# AP7387Q.net
KiCad netlist of a schematic drawn in Altium Designer
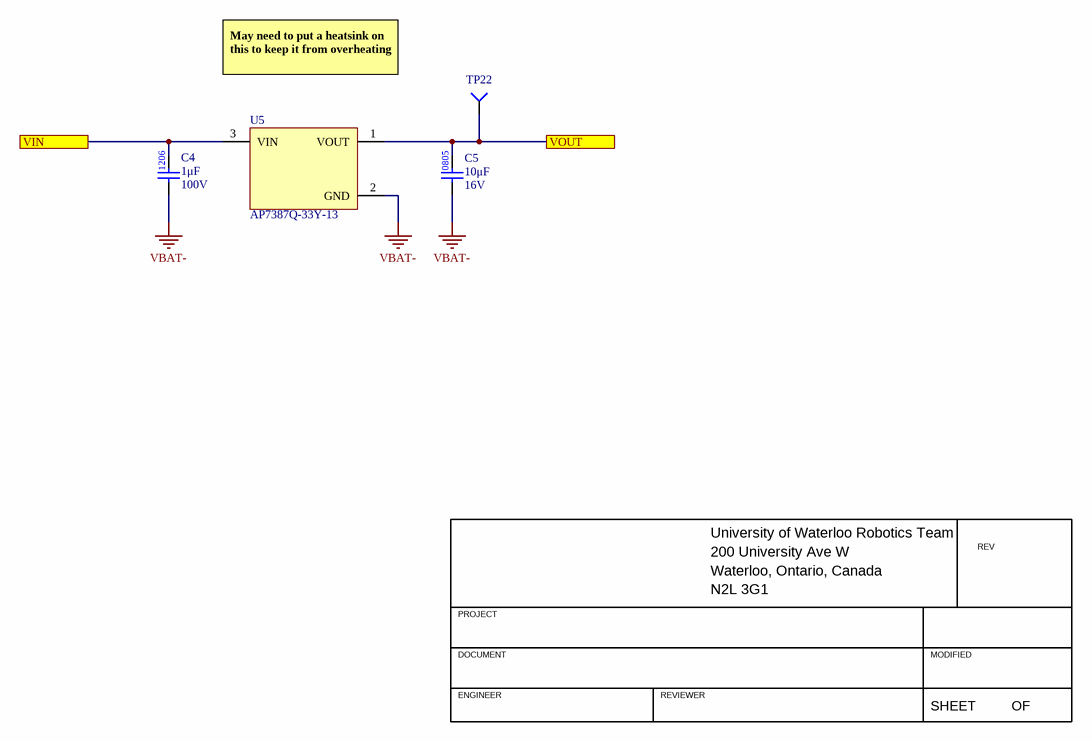
[diagram p0: AP7387Q.SchDoc]

(export (version "E")
  (design (tool "Eeschema 10.0.6"))
  (components
    (comp (ref "C4")
      (value "1μF")
      (footprint "CAPC3216X190X50NL20T25")
      (description "CAP CER 1UF 100V X7R 1206")
      (fields (field (name "VOLTAGE RATING") "100V") (field (name "Comment") "CAP_1uF_100V_1206"))
      (libsource (lib "Personal_Schematic_Library_2022") (part "CAP_1uF_100V_1206"))
    )
    (comp (ref "C5")
      (value "10μF")
      (footprint "CAP2012")
      (description "CAP CER 10UF 16V X5R 0805")
      (fields (field (name "VOLTAGE RATING") "16V") (field (name "Comment") "CAP_10uF_16V_0805"))
      (libsource (lib "Personal_Schematic_Library_2022") (part "CAP_10uF_16V_0805"))
    )
    (comp (ref "TP22")
      (value "TESTPOINT_SMD_LOOP")
      (footprint "S1751-46R")
      (description "TESTPOINT SMD LOOP")
      (libsource (lib "UWRT_Schematic_Library_2020") (part "TESTPOINT_SMD_LOOP"))
    )
    (comp (ref "U5")
      (value "LDO_3.3V_150mA_60VIN")
      (footprint "SOT89")
      (description "IC REG LINEAR 3.3V 150MA SOT89-3")
      (fields (field (name "MANUFACTURER PART NUMBER 1") "AP7387Q-33Y-13"))
      (libsource (lib "Personal_Schematic_Library_2022") (part "LDO_3.3V_150mA_60VIN"))
    )
  )
  (nets
    (net (code "1") (name "/VIN") (class "Default")
      (node (ref "C4") (pin "2") (pinfunction "2_2") (pintype "passive"))
      (node (ref "U5") (pin "3") (pinfunction "VIN_3") (pintype "power_in"))
    )
    (net (code "2") (name "/VOUT") (class "Default")
      (node (ref "C5") (pin "2") (pinfunction "2_2") (pintype "passive"))
      (node (ref "TP22") (pin "1") (pinfunction "=value_1") (pintype "passive"))
      (node (ref "U5") (pin "1") (pinfunction "VOUT_1") (pintype "power_in"))
    )
    (net (code "3") (name "VBAT-") (class "Default")
      (node (ref "C4") (pin "1") (pinfunction "1_1") (pintype "passive"))
      (node (ref "C5") (pin "1") (pinfunction "1_1") (pintype "passive"))
      (node (ref "U5") (pin "2") (pinfunction "GND_2") (pintype "power_in"))
    )
  )
)
